# 009.net
KiCad netlist of a schematic drawn in EAGLE
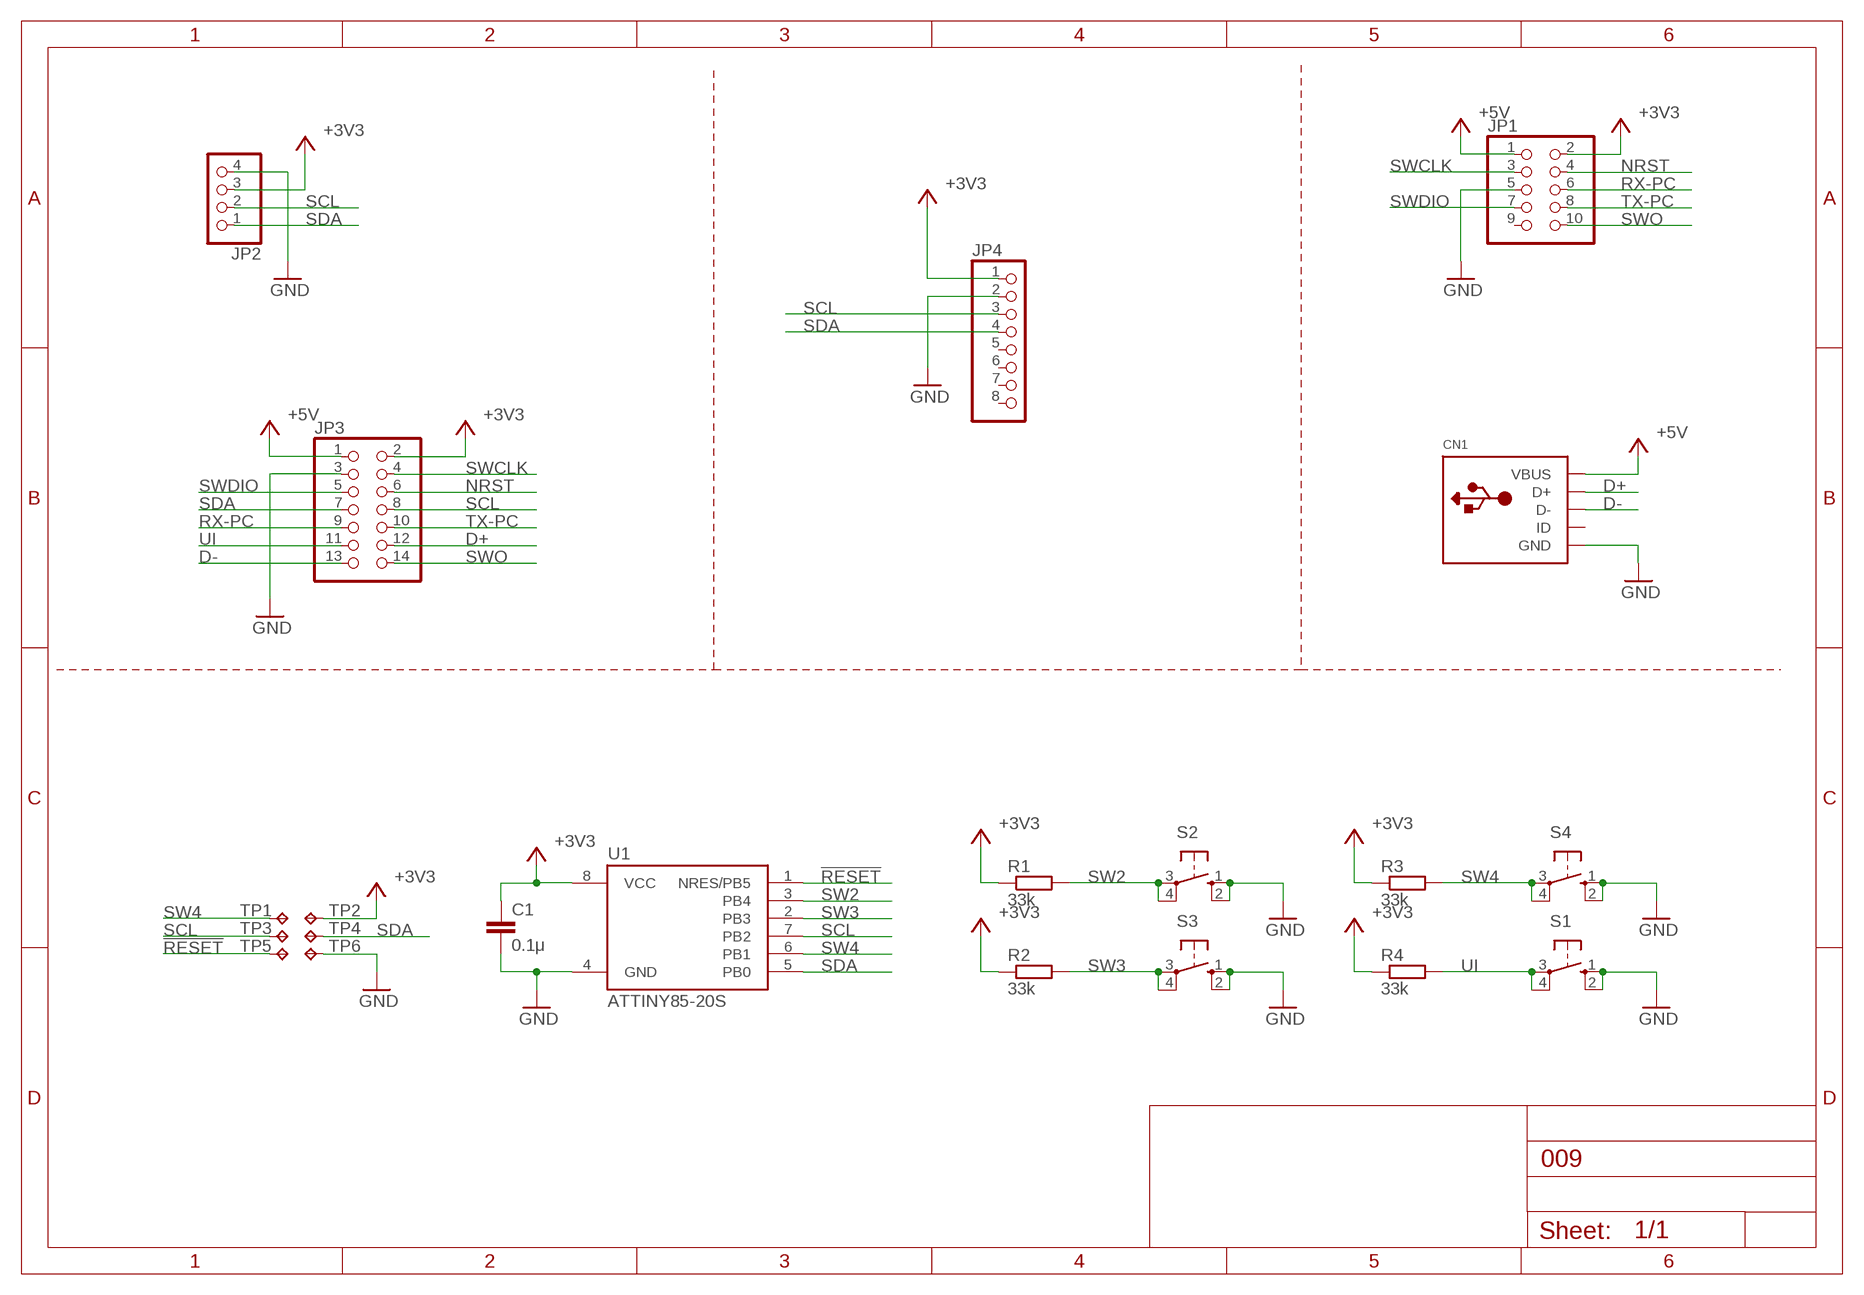
[diagram p0: schematic, sheet 1]

(export (version "E")
  (design (tool "Eeschema 10.0.6"))
  (components
    (comp (ref "C1")
      (value "0.1μ")
      (footprint "eagle-import:C0603")
      (libsource (lib "eagle-import") (part "C-EUC0603"))
    )
    (comp (ref "CN1")
      (value "USBTHM")
      (footprint "eagle-import:USB-MINIB-THM")
      (libsource (lib "eagle-import") (part "USBTHM"))
    )
    (comp (ref "JP1")
      (value "PINHD-2X5")
      (footprint "eagle-import:2X05")
      (libsource (lib "eagle-import") (part "PINHD-2X5"))
    )
    (comp (ref "JP2")
      (value "PINHD-1X4")
      (footprint "eagle-import:1X04")
      (libsource (lib "eagle-import") (part "PINHD-1X4"))
    )
    (comp (ref "JP3")
      (value "PINHD-2X7/90")
      (footprint "eagle-import:2X07_90")
      (libsource (lib "eagle-import") (part "PINHD-2X7/90"))
    )
    (comp (ref "JP4")
      (value "PINHD-1X8")
      (footprint "eagle-import:1X08")
      (libsource (lib "eagle-import") (part "PINHD-1X8"))
    )
    (comp (ref "R1")
      (value "33k")
      (footprint "eagle-import:R0603")
      (libsource (lib "eagle-import") (part "R-EU_R0603"))
    )
    (comp (ref "R2")
      (value "33k")
      (footprint "eagle-import:R0603")
      (libsource (lib "eagle-import") (part "R-EU_R0603"))
    )
    (comp (ref "R3")
      (value "33k")
      (footprint "eagle-import:R0603")
      (libsource (lib "eagle-import") (part "R-EU_R0603"))
    )
    (comp (ref "R4")
      (value "33k")
      (footprint "eagle-import:R0603")
      (libsource (lib "eagle-import") (part "R-EU_R0603"))
    )
    (comp (ref "S1")
      (value "40-XX")
      (footprint "eagle-import:B3F-40XX")
      (fields (field (name "MF") "OMRON COMPONENTS USA") (field (name "MPN") "B3F-4000"))
      (libsource (lib "eagle-import") (part "40-XX"))
    )
    (comp (ref "S2")
      (value "40-XX")
      (footprint "eagle-import:B3F-40XX")
      (fields (field (name "MF") "OMRON COMPONENTS USA") (field (name "MPN") "B3F-4000"))
      (libsource (lib "eagle-import") (part "40-XX"))
    )
    (comp (ref "S3")
      (value "10-XX")
      (footprint "eagle-import:B3F-10XX")
      (fields (field (name "MPN") "B3F-1000"))
      (libsource (lib "eagle-import") (part "10-XX"))
    )
    (comp (ref "S4")
      (value "10-XX")
      (footprint "eagle-import:B3F-10XX")
      (fields (field (name "MPN") "B3F-1000"))
      (libsource (lib "eagle-import") (part "10-XX"))
    )
    (comp (ref "TP1")
      (value "TPTP15SQ")
      (footprint "eagle-import:TP15SQ")
      (libsource (lib "eagle-import") (part "TPTP15SQ"))
    )
    (comp (ref "TP2")
      (value "TPTP15R")
      (footprint "eagle-import:TP15R")
      (libsource (lib "eagle-import") (part "TPTP15R"))
    )
    (comp (ref "TP3")
      (value "TPTP15R")
      (footprint "eagle-import:TP15R")
      (libsource (lib "eagle-import") (part "TPTP15R"))
    )
    (comp (ref "TP4")
      (value "TPTP15R")
      (footprint "eagle-import:TP15R")
      (libsource (lib "eagle-import") (part "TPTP15R"))
    )
    (comp (ref "TP5")
      (value "TPTP15R")
      (footprint "eagle-import:TP15R")
      (libsource (lib "eagle-import") (part "TPTP15R"))
    )
    (comp (ref "TP6")
      (value "TPTP15R")
      (footprint "eagle-import:TP15R")
      (libsource (lib "eagle-import") (part "TPTP15R"))
    )
    (comp (ref "U1")
      (value "ATTINY85-20S")
      (footprint "eagle-import:SOIC8_EIAJ_208MIL")
      (libsource (lib "eagle-import") (part "ATTINY85S-20"))
    )
  )
  (nets
    (net (code "1") (name "+3V3") (class "Default")
      (node (ref "C1") (pin "1") (pinfunction "1_1") (pintype "passive"))
      (node (ref "JP1") (pin "2") (pinfunction "2_2") (pintype "passive"))
      (node (ref "JP2") (pin "3") (pinfunction "3_3") (pintype "passive"))
      (node (ref "JP3") (pin "2") (pinfunction "2_2") (pintype "passive"))
      (node (ref "JP4") (pin "1") (pinfunction "1_1") (pintype "passive"))
      (node (ref "R1") (pin "1") (pinfunction "1_1") (pintype "passive"))
      (node (ref "R2") (pin "1") (pinfunction "1_1") (pintype "passive"))
      (node (ref "R3") (pin "1") (pinfunction "1_1") (pintype "passive"))
      (node (ref "R4") (pin "1") (pinfunction "1_1") (pintype "passive"))
      (node (ref "TP2") (pin "TP") (pinfunction "TP_TP") (pintype "input"))
      (node (ref "U1") (pin "8") (pinfunction "VCC_8") (pintype "power_in"))
    )
    (net (code "2") (name "+5V") (class "Default")
      (node (ref "CN1") (pin "VBUS") (pinfunction "VBUS_VBUS") (pintype "power_in"))
      (node (ref "JP1") (pin "1") (pinfunction "1_1") (pintype "passive"))
      (node (ref "JP3") (pin "1") (pinfunction "1_1") (pintype "passive"))
    )
    (net (code "3") (name "/D+") (class "Default")
      (node (ref "CN1") (pin "D+") (pinfunction "D+_D+") (pintype "bidirectional"))
      (node (ref "JP3") (pin "12") (pinfunction "12_12") (pintype "passive"))
    )
    (net (code "4") (name "/D-") (class "Default")
      (node (ref "CN1") (pin "D-") (pinfunction "D-_D-") (pintype "bidirectional"))
      (node (ref "JP3") (pin "13") (pinfunction "13_13") (pintype "passive"))
    )
    (net (code "5") (name "/NRST") (class "Default")
      (node (ref "JP1") (pin "4") (pinfunction "4_4") (pintype "passive"))
      (node (ref "JP3") (pin "6") (pinfunction "6_6") (pintype "passive"))
    )
    (net (code "6") (name "/RX-PC") (class "Default")
      (node (ref "JP1") (pin "6") (pinfunction "6_6") (pintype "passive"))
      (node (ref "JP3") (pin "9") (pinfunction "9_9") (pintype "passive"))
    )
    (net (code "7") (name "/SCL") (class "Default")
      (node (ref "JP2") (pin "2") (pinfunction "2_2") (pintype "passive"))
      (node (ref "JP3") (pin "8") (pinfunction "8_8") (pintype "passive"))
      (node (ref "JP4") (pin "3") (pinfunction "3_3") (pintype "passive"))
      (node (ref "TP3") (pin "TP") (pinfunction "TP_TP") (pintype "input"))
      (node (ref "U1") (pin "7") (pinfunction "PB2_7") (pintype "bidirectional"))
    )
    (net (code "8") (name "/SDA") (class "Default")
      (node (ref "JP2") (pin "1") (pinfunction "1_1") (pintype "passive"))
      (node (ref "JP3") (pin "7") (pinfunction "7_7") (pintype "passive"))
      (node (ref "JP4") (pin "4") (pinfunction "4_4") (pintype "passive"))
      (node (ref "TP4") (pin "TP") (pinfunction "TP_TP") (pintype "input"))
      (node (ref "U1") (pin "5") (pinfunction "PB0_5") (pintype "bidirectional"))
    )
    (net (code "9") (name "/SW2") (class "Default")
      (node (ref "R1") (pin "2") (pinfunction "2_2") (pintype "passive"))
      (node (ref "S2") (pin "3") (pinfunction "P_3") (pintype "passive"))
      (node (ref "S2") (pin "4") (pinfunction "P1_4") (pintype "passive"))
      (node (ref "U1") (pin "3") (pinfunction "PB4_3") (pintype "bidirectional"))
    )
    (net (code "10") (name "/SW3") (class "Default")
      (node (ref "R2") (pin "2") (pinfunction "2_2") (pintype "passive"))
      (node (ref "S3") (pin "3") (pinfunction "P_3") (pintype "passive"))
      (node (ref "S3") (pin "4") (pinfunction "P1_4") (pintype "passive"))
      (node (ref "U1") (pin "2") (pinfunction "PB3_2") (pintype "bidirectional"))
    )
    (net (code "11") (name "/SW4") (class "Default")
      (node (ref "R3") (pin "2") (pinfunction "2_2") (pintype "passive"))
      (node (ref "S4") (pin "3") (pinfunction "P_3") (pintype "passive"))
      (node (ref "S4") (pin "4") (pinfunction "P1_4") (pintype "passive"))
      (node (ref "TP1") (pin "TP") (pinfunction "TP_TP") (pintype "input"))
      (node (ref "U1") (pin "6") (pinfunction "PB1_6") (pintype "bidirectional"))
    )
    (net (code "12") (name "/SWCLK") (class "Default")
      (node (ref "JP1") (pin "3") (pinfunction "3_3") (pintype "passive"))
      (node (ref "JP3") (pin "4") (pinfunction "4_4") (pintype "passive"))
    )
    (net (code "13") (name "/SWDIO") (class "Default")
      (node (ref "JP1") (pin "7") (pinfunction "7_7") (pintype "passive"))
      (node (ref "JP3") (pin "5") (pinfunction "5_5") (pintype "passive"))
    )
    (net (code "14") (name "/SWO") (class "Default")
      (node (ref "JP1") (pin "10") (pinfunction "10_10") (pintype "passive"))
      (node (ref "JP3") (pin "14") (pinfunction "14_14") (pintype "passive"))
    )
    (net (code "15") (name "/TX-PC") (class "Default")
      (node (ref "JP1") (pin "8") (pinfunction "8_8") (pintype "passive"))
      (node (ref "JP3") (pin "10") (pinfunction "10_10") (pintype "passive"))
    )
    (net (code "16") (name "/UI") (class "Default")
      (node (ref "JP3") (pin "11") (pinfunction "11_11") (pintype "passive"))
      (node (ref "R4") (pin "2") (pinfunction "2_2") (pintype "passive"))
      (node (ref "S1") (pin "3") (pinfunction "P_3") (pintype "passive"))
      (node (ref "S1") (pin "4") (pinfunction "P1_4") (pintype "passive"))
    )
    (net (code "17") (name "/~{RESET}") (class "Default")
      (node (ref "TP5") (pin "TP") (pinfunction "TP_TP") (pintype "input"))
      (node (ref "U1") (pin "1") (pinfunction "NRES/PB5_1") (pintype "bidirectional"))
    )
    (net (code "18") (name "GND") (class "Default")
      (node (ref "C1") (pin "2") (pinfunction "2_2") (pintype "passive"))
      (node (ref "CN1") (pin "GND") (pinfunction "GND_GND") (pintype "power_in"))
      (node (ref "JP1") (pin "5") (pinfunction "5_5") (pintype "passive"))
      (node (ref "JP2") (pin "4") (pinfunction "4_4") (pintype "passive"))
      (node (ref "JP3") (pin "3") (pinfunction "3_3") (pintype "passive"))
      (node (ref "JP4") (pin "2") (pinfunction "2_2") (pintype "passive"))
      (node (ref "S1") (pin "1") (pinfunction "S_1") (pintype "passive"))
      (node (ref "S1") (pin "2") (pinfunction "S1_2") (pintype "passive"))
      (node (ref "S2") (pin "1") (pinfunction "S_1") (pintype "passive"))
      (node (ref "S2") (pin "2") (pinfunction "S1_2") (pintype "passive"))
      (node (ref "S3") (pin "1") (pinfunction "S_1") (pintype "passive"))
      (node (ref "S3") (pin "2") (pinfunction "S1_2") (pintype "passive"))
      (node (ref "S4") (pin "1") (pinfunction "S_1") (pintype "passive"))
      (node (ref "S4") (pin "2") (pinfunction "S1_2") (pintype "passive"))
      (node (ref "TP6") (pin "TP") (pinfunction "TP_TP") (pintype "input"))
      (node (ref "U1") (pin "4") (pinfunction "GND_4") (pintype "power_in"))
    )
    (net (code "19") (name "unconnected-(CN1-PadID)") (class "Default")
      (node (ref "CN1") (pin "ID") (pinfunction "ID_ID") (pintype "bidirectional"))
    )
    (net (code "20") (name "unconnected-(JP1-Pad9)") (class "Default")
      (node (ref "JP1") (pin "9") (pinfunction "9_9") (pintype "passive"))
    )
    (net (code "21") (name "unconnected-(JP4-Pad5)") (class "Default")
      (node (ref "JP4") (pin "5") (pinfunction "5_5") (pintype "passive"))
    )
    (net (code "22") (name "unconnected-(JP4-Pad6)") (class "Default")
      (node (ref "JP4") (pin "6") (pinfunction "6_6") (pintype "passive"))
    )
    (net (code "23") (name "unconnected-(JP4-Pad7)") (class "Default")
      (node (ref "JP4") (pin "7") (pinfunction "7_7") (pintype "passive"))
    )
    (net (code "24") (name "unconnected-(JP4-Pad8)") (class "Default")
      (node (ref "JP4") (pin "8") (pinfunction "8_8") (pintype "passive"))
    )
  )
)
